# con-top-j3-0.net
KiCad netlist of a schematic drawn in Altium Designer
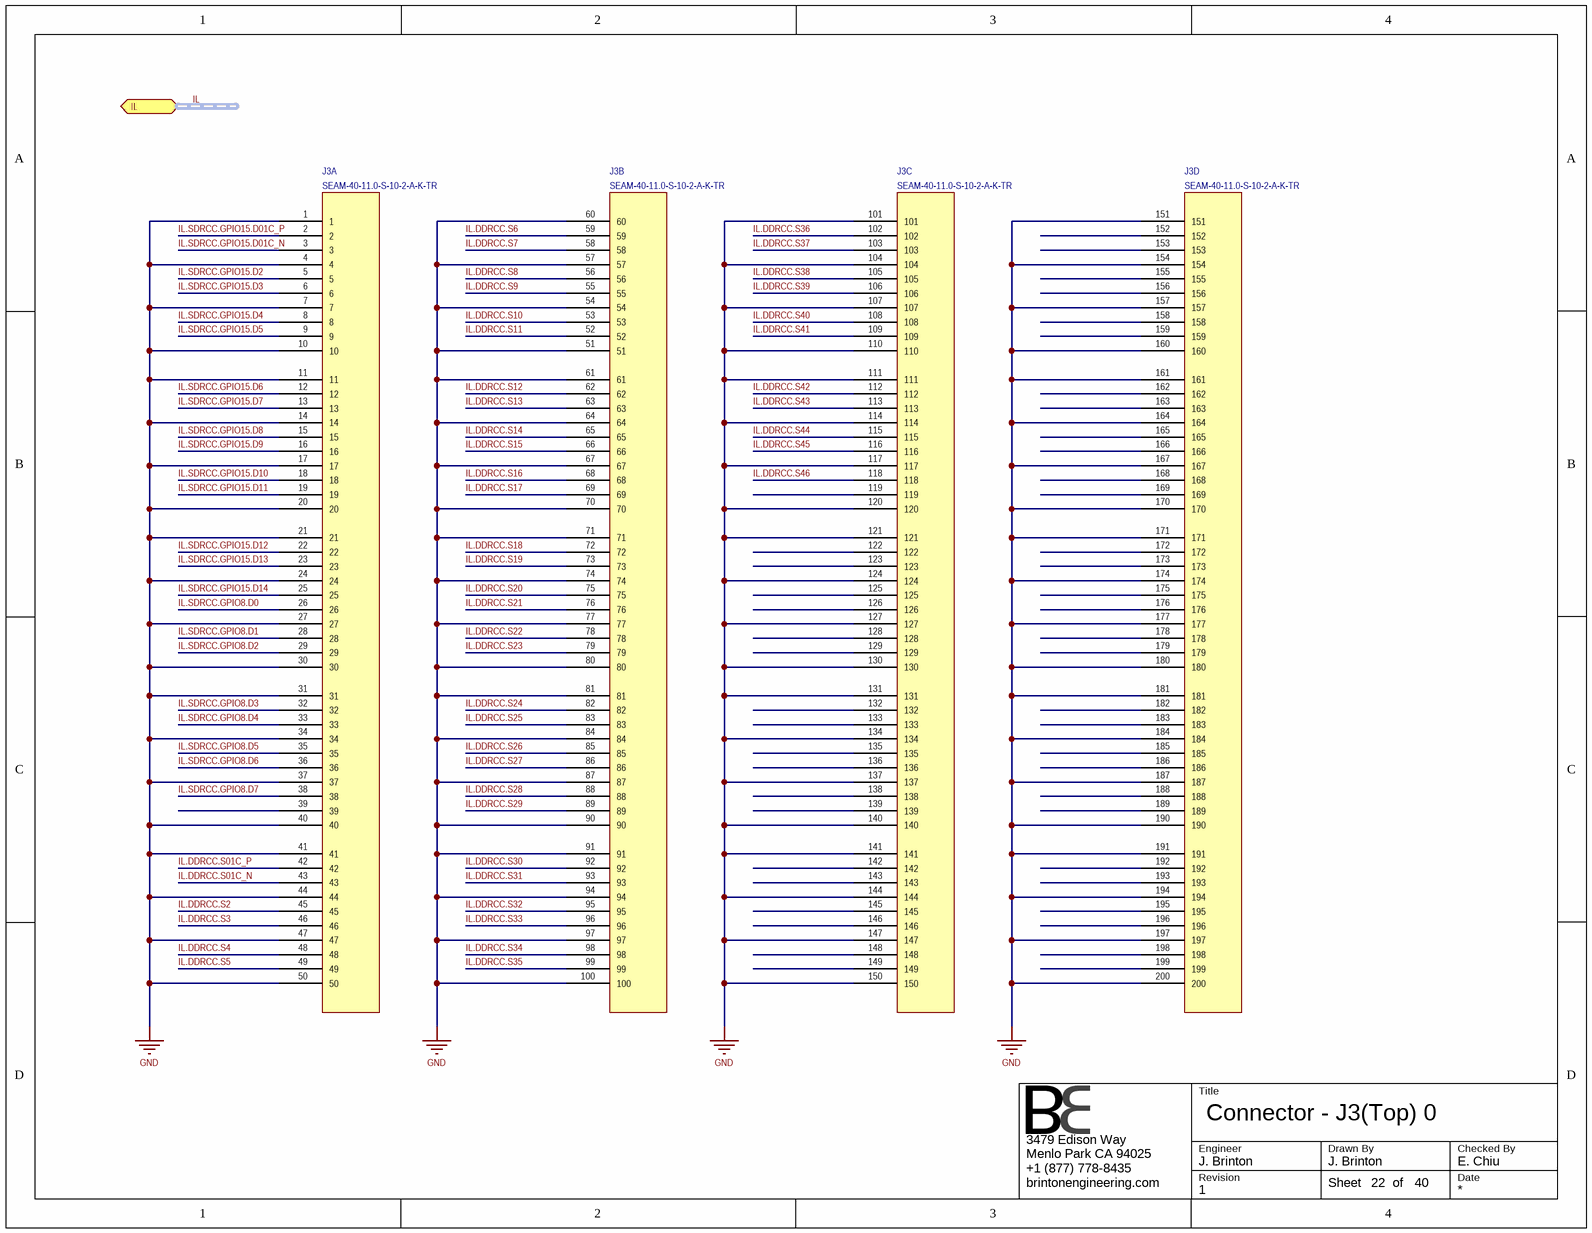
[diagram p0: con-top-j3-0.SchDoc]

(export (version "E")
  (design (tool "Eeschema 10.0.6"))
  (components
    (comp (ref "J3")
      (value "SEAM-40-11.0-S-10-2-A-K-TR")
      (footprint "samtec:SEAM-40-11.0-S-10-2-A-K-TR")
      (description "Terminal Array Assembly, Surface Mount, 0.050\" Pitch, 400 Pins")
      (fields (field (name "MANUFACTURER") "Samtec"))
      (libsource (lib "samtec") (part "SEAM-40-11.0-S-10-2-A-K-TR"))
    )
  )
  (nets
    (net (code "2") (name "/IL.DDRCC.S01C_N") (class "Default")
      (node (ref "J3") (pin "43") (pinfunction "43_43") (pintype "passive"))
    )
    (net (code "3") (name "/IL.DDRCC.S01C_P") (class "Default")
      (node (ref "J3") (pin "42") (pinfunction "42_42") (pintype "passive"))
    )
    (net (code "4") (name "/IL.DDRCC.S2") (class "Default")
      (node (ref "J3") (pin "45") (pinfunction "45_45") (pintype "passive"))
    )
    (net (code "5") (name "/IL.DDRCC.S3") (class "Default")
      (node (ref "J3") (pin "46") (pinfunction "46_46") (pintype "passive"))
    )
    (net (code "6") (name "/IL.DDRCC.S4") (class "Default")
      (node (ref "J3") (pin "48") (pinfunction "48_48") (pintype "passive"))
    )
    (net (code "7") (name "/IL.DDRCC.S5") (class "Default")
      (node (ref "J3") (pin "49") (pinfunction "49_49") (pintype "passive"))
    )
    (net (code "8") (name "/IL.DDRCC.S6") (class "Default")
      (node (ref "J3") (pin "59") (pinfunction "59_59") (pintype "passive"))
    )
    (net (code "9") (name "/IL.DDRCC.S7") (class "Default")
      (node (ref "J3") (pin "58") (pinfunction "58_58") (pintype "passive"))
    )
    (net (code "10") (name "/IL.DDRCC.S8") (class "Default")
      (node (ref "J3") (pin "56") (pinfunction "56_56") (pintype "passive"))
    )
    (net (code "11") (name "/IL.DDRCC.S9") (class "Default")
      (node (ref "J3") (pin "55") (pinfunction "55_55") (pintype "passive"))
    )
    (net (code "12") (name "/IL.DDRCC.S10") (class "Default")
      (node (ref "J3") (pin "53") (pinfunction "53_53") (pintype "passive"))
    )
    (net (code "13") (name "/IL.DDRCC.S11") (class "Default")
      (node (ref "J3") (pin "52") (pinfunction "52_52") (pintype "passive"))
    )
    (net (code "14") (name "/IL.DDRCC.S12") (class "Default")
      (node (ref "J3") (pin "62") (pinfunction "62_62") (pintype "passive"))
    )
    (net (code "15") (name "/IL.DDRCC.S13") (class "Default")
      (node (ref "J3") (pin "63") (pinfunction "63_63") (pintype "passive"))
    )
    (net (code "16") (name "/IL.DDRCC.S14") (class "Default")
      (node (ref "J3") (pin "65") (pinfunction "65_65") (pintype "passive"))
    )
    (net (code "17") (name "/IL.DDRCC.S15") (class "Default")
      (node (ref "J3") (pin "66") (pinfunction "66_66") (pintype "passive"))
    )
    (net (code "18") (name "/IL.DDRCC.S16") (class "Default")
      (node (ref "J3") (pin "68") (pinfunction "68_68") (pintype "passive"))
    )
    (net (code "19") (name "/IL.DDRCC.S17") (class "Default")
      (node (ref "J3") (pin "69") (pinfunction "69_69") (pintype "passive"))
    )
    (net (code "20") (name "/IL.DDRCC.S18") (class "Default")
      (node (ref "J3") (pin "72") (pinfunction "72_72") (pintype "passive"))
    )
    (net (code "21") (name "/IL.DDRCC.S19") (class "Default")
      (node (ref "J3") (pin "73") (pinfunction "73_73") (pintype "passive"))
    )
    (net (code "22") (name "/IL.DDRCC.S20") (class "Default")
      (node (ref "J3") (pin "75") (pinfunction "75_75") (pintype "passive"))
    )
    (net (code "23") (name "/IL.DDRCC.S21") (class "Default")
      (node (ref "J3") (pin "76") (pinfunction "76_76") (pintype "passive"))
    )
    (net (code "24") (name "/IL.DDRCC.S22") (class "Default")
      (node (ref "J3") (pin "78") (pinfunction "78_78") (pintype "passive"))
    )
    (net (code "25") (name "/IL.DDRCC.S23") (class "Default")
      (node (ref "J3") (pin "79") (pinfunction "79_79") (pintype "passive"))
    )
    (net (code "26") (name "/IL.DDRCC.S24") (class "Default")
      (node (ref "J3") (pin "82") (pinfunction "82_82") (pintype "passive"))
    )
    (net (code "27") (name "/IL.DDRCC.S25") (class "Default")
      (node (ref "J3") (pin "83") (pinfunction "83_83") (pintype "passive"))
    )
    (net (code "28") (name "/IL.DDRCC.S26") (class "Default")
      (node (ref "J3") (pin "85") (pinfunction "85_85") (pintype "passive"))
    )
    (net (code "29") (name "/IL.DDRCC.S27") (class "Default")
      (node (ref "J3") (pin "86") (pinfunction "86_86") (pintype "passive"))
    )
    (net (code "30") (name "/IL.DDRCC.S28") (class "Default")
      (node (ref "J3") (pin "88") (pinfunction "88_88") (pintype "passive"))
    )
    (net (code "31") (name "/IL.DDRCC.S29") (class "Default")
      (node (ref "J3") (pin "89") (pinfunction "89_89") (pintype "passive"))
    )
    (net (code "32") (name "/IL.DDRCC.S30") (class "Default")
      (node (ref "J3") (pin "92") (pinfunction "92_92") (pintype "passive"))
    )
    (net (code "33") (name "/IL.DDRCC.S31") (class "Default")
      (node (ref "J3") (pin "93") (pinfunction "93_93") (pintype "passive"))
    )
    (net (code "34") (name "/IL.DDRCC.S32") (class "Default")
      (node (ref "J3") (pin "95") (pinfunction "95_95") (pintype "passive"))
    )
    (net (code "35") (name "/IL.DDRCC.S33") (class "Default")
      (node (ref "J3") (pin "96") (pinfunction "96_96") (pintype "passive"))
    )
    (net (code "36") (name "/IL.DDRCC.S34") (class "Default")
      (node (ref "J3") (pin "98") (pinfunction "98_98") (pintype "passive"))
    )
    (net (code "37") (name "/IL.DDRCC.S35") (class "Default")
      (node (ref "J3") (pin "99") (pinfunction "99_99") (pintype "passive"))
    )
    (net (code "38") (name "/IL.DDRCC.S36") (class "Default")
      (node (ref "J3") (pin "102") (pinfunction "102_102") (pintype "passive"))
    )
    (net (code "39") (name "/IL.DDRCC.S37") (class "Default")
      (node (ref "J3") (pin "103") (pinfunction "103_103") (pintype "passive"))
    )
    (net (code "40") (name "/IL.DDRCC.S38") (class "Default")
      (node (ref "J3") (pin "105") (pinfunction "105_105") (pintype "passive"))
    )
    (net (code "41") (name "/IL.DDRCC.S39") (class "Default")
      (node (ref "J3") (pin "106") (pinfunction "106_106") (pintype "passive"))
    )
    (net (code "42") (name "/IL.DDRCC.S40") (class "Default")
      (node (ref "J3") (pin "108") (pinfunction "108_108") (pintype "passive"))
    )
    (net (code "43") (name "/IL.DDRCC.S41") (class "Default")
      (node (ref "J3") (pin "109") (pinfunction "109_109") (pintype "passive"))
    )
    (net (code "44") (name "/IL.DDRCC.S42") (class "Default")
      (node (ref "J3") (pin "112") (pinfunction "112_112") (pintype "passive"))
    )
    (net (code "45") (name "/IL.DDRCC.S43") (class "Default")
      (node (ref "J3") (pin "113") (pinfunction "113_113") (pintype "passive"))
    )
    (net (code "46") (name "/IL.DDRCC.S44") (class "Default")
      (node (ref "J3") (pin "115") (pinfunction "115_115") (pintype "passive"))
    )
    (net (code "47") (name "/IL.DDRCC.S45") (class "Default")
      (node (ref "J3") (pin "116") (pinfunction "116_116") (pintype "passive"))
    )
    (net (code "48") (name "/IL.DDRCC.S46") (class "Default")
      (node (ref "J3") (pin "118") (pinfunction "118_118") (pintype "passive"))
    )
    (net (code "49") (name "/IL.SDRCC.GPIO8.D0") (class "Default")
      (node (ref "J3") (pin "26") (pinfunction "26_26") (pintype "passive"))
    )
    (net (code "50") (name "/IL.SDRCC.GPIO8.D1") (class "Default")
      (node (ref "J3") (pin "28") (pinfunction "28_28") (pintype "passive"))
    )
    (net (code "51") (name "/IL.SDRCC.GPIO8.D2") (class "Default")
      (node (ref "J3") (pin "29") (pinfunction "29_29") (pintype "passive"))
    )
    (net (code "52") (name "/IL.SDRCC.GPIO8.D3") (class "Default")
      (node (ref "J3") (pin "32") (pinfunction "32_32") (pintype "passive"))
    )
    (net (code "53") (name "/IL.SDRCC.GPIO8.D4") (class "Default")
      (node (ref "J3") (pin "33") (pinfunction "33_33") (pintype "passive"))
    )
    (net (code "54") (name "/IL.SDRCC.GPIO8.D5") (class "Default")
      (node (ref "J3") (pin "35") (pinfunction "35_35") (pintype "passive"))
    )
    (net (code "55") (name "/IL.SDRCC.GPIO8.D6") (class "Default")
      (node (ref "J3") (pin "36") (pinfunction "36_36") (pintype "passive"))
    )
    (net (code "56") (name "/IL.SDRCC.GPIO8.D7") (class "Default")
      (node (ref "J3") (pin "38") (pinfunction "38_38") (pintype "passive"))
    )
    (net (code "57") (name "/IL.SDRCC.GPIO15.D01C_N") (class "Default")
      (node (ref "J3") (pin "3") (pinfunction "3_3") (pintype "passive"))
    )
    (net (code "58") (name "/IL.SDRCC.GPIO15.D01C_P") (class "Default")
      (node (ref "J3") (pin "2") (pinfunction "2_2") (pintype "passive"))
    )
    (net (code "59") (name "/IL.SDRCC.GPIO15.D2") (class "Default")
      (node (ref "J3") (pin "5") (pinfunction "5_5") (pintype "passive"))
    )
    (net (code "60") (name "/IL.SDRCC.GPIO15.D3") (class "Default")
      (node (ref "J3") (pin "6") (pinfunction "6_6") (pintype "passive"))
    )
    (net (code "61") (name "/IL.SDRCC.GPIO15.D4") (class "Default")
      (node (ref "J3") (pin "8") (pinfunction "8_8") (pintype "passive"))
    )
    (net (code "62") (name "/IL.SDRCC.GPIO15.D5") (class "Default")
      (node (ref "J3") (pin "9") (pinfunction "9_9") (pintype "passive"))
    )
    (net (code "63") (name "/IL.SDRCC.GPIO15.D6") (class "Default")
      (node (ref "J3") (pin "12") (pinfunction "12_12") (pintype "passive"))
    )
    (net (code "64") (name "/IL.SDRCC.GPIO15.D7") (class "Default")
      (node (ref "J3") (pin "13") (pinfunction "13_13") (pintype "passive"))
    )
    (net (code "65") (name "/IL.SDRCC.GPIO15.D8") (class "Default")
      (node (ref "J3") (pin "15") (pinfunction "15_15") (pintype "passive"))
    )
    (net (code "66") (name "/IL.SDRCC.GPIO15.D9") (class "Default")
      (node (ref "J3") (pin "16") (pinfunction "16_16") (pintype "passive"))
    )
    (net (code "67") (name "/IL.SDRCC.GPIO15.D10") (class "Default")
      (node (ref "J3") (pin "18") (pinfunction "18_18") (pintype "passive"))
    )
    (net (code "68") (name "/IL.SDRCC.GPIO15.D11") (class "Default")
      (node (ref "J3") (pin "19") (pinfunction "19_19") (pintype "passive"))
    )
    (net (code "69") (name "/IL.SDRCC.GPIO15.D12") (class "Default")
      (node (ref "J3") (pin "22") (pinfunction "22_22") (pintype "passive"))
    )
    (net (code "70") (name "/IL.SDRCC.GPIO15.D13") (class "Default")
      (node (ref "J3") (pin "23") (pinfunction "23_23") (pintype "passive"))
    )
    (net (code "71") (name "/IL.SDRCC.GPIO15.D14") (class "Default")
      (node (ref "J3") (pin "25") (pinfunction "25_25") (pintype "passive"))
    )
    (net (code "73") (name "GND") (class "Default")
      (node (ref "J3") (pin "1") (pinfunction "1_1") (pintype "passive"))
      (node (ref "J3") (pin "10") (pinfunction "10_10") (pintype "passive"))
      (node (ref "J3") (pin "100") (pinfunction "100_100") (pintype "passive"))
      (node (ref "J3") (pin "101") (pinfunction "101_101") (pintype "passive"))
      (node (ref "J3") (pin "104") (pinfunction "104_104") (pintype "passive"))
      (node (ref "J3") (pin "107") (pinfunction "107_107") (pintype "passive"))
      (node (ref "J3") (pin "11") (pinfunction "11_11") (pintype "passive"))
      (node (ref "J3") (pin "110") (pinfunction "110_110") (pintype "passive"))
      (node (ref "J3") (pin "111") (pinfunction "111_111") (pintype "passive"))
      (node (ref "J3") (pin "114") (pinfunction "114_114") (pintype "passive"))
      (node (ref "J3") (pin "117") (pinfunction "117_117") (pintype "passive"))
      (node (ref "J3") (pin "120") (pinfunction "120_120") (pintype "passive"))
      (node (ref "J3") (pin "121") (pinfunction "121_121") (pintype "passive"))
      (node (ref "J3") (pin "124") (pinfunction "124_124") (pintype "passive"))
      (node (ref "J3") (pin "127") (pinfunction "127_127") (pintype "passive"))
      (node (ref "J3") (pin "130") (pinfunction "130_130") (pintype "passive"))
      (node (ref "J3") (pin "131") (pinfunction "131_131") (pintype "passive"))
      (node (ref "J3") (pin "134") (pinfunction "134_134") (pintype "passive"))
      (node (ref "J3") (pin "137") (pinfunction "137_137") (pintype "passive"))
      (node (ref "J3") (pin "14") (pinfunction "14_14") (pintype "passive"))
      (node (ref "J3") (pin "140") (pinfunction "140_140") (pintype "passive"))
      (node (ref "J3") (pin "141") (pinfunction "141_141") (pintype "passive"))
      (node (ref "J3") (pin "144") (pinfunction "144_144") (pintype "passive"))
      (node (ref "J3") (pin "147") (pinfunction "147_147") (pintype "passive"))
      (node (ref "J3") (pin "150") (pinfunction "150_150") (pintype "passive"))
      (node (ref "J3") (pin "151") (pinfunction "151_151") (pintype "passive"))
      (node (ref "J3") (pin "154") (pinfunction "154_154") (pintype "passive"))
      (node (ref "J3") (pin "157") (pinfunction "157_157") (pintype "passive"))
      (node (ref "J3") (pin "160") (pinfunction "160_160") (pintype "passive"))
      (node (ref "J3") (pin "161") (pinfunction "161_161") (pintype "passive"))
      (node (ref "J3") (pin "164") (pinfunction "164_164") (pintype "passive"))
      (node (ref "J3") (pin "167") (pinfunction "167_167") (pintype "passive"))
      (node (ref "J3") (pin "17") (pinfunction "17_17") (pintype "passive"))
      (node (ref "J3") (pin "170") (pinfunction "170_170") (pintype "passive"))
      (node (ref "J3") (pin "171") (pinfunction "171_171") (pintype "passive"))
      (node (ref "J3") (pin "174") (pinfunction "174_174") (pintype "passive"))
      (node (ref "J3") (pin "177") (pinfunction "177_177") (pintype "passive"))
      (node (ref "J3") (pin "180") (pinfunction "180_180") (pintype "passive"))
      (node (ref "J3") (pin "181") (pinfunction "181_181") (pintype "passive"))
      (node (ref "J3") (pin "184") (pinfunction "184_184") (pintype "passive"))
      (node (ref "J3") (pin "187") (pinfunction "187_187") (pintype "passive"))
      (node (ref "J3") (pin "190") (pinfunction "190_190") (pintype "passive"))
      (node (ref "J3") (pin "191") (pinfunction "191_191") (pintype "passive"))
      (node (ref "J3") (pin "194") (pinfunction "194_194") (pintype "passive"))
      (node (ref "J3") (pin "197") (pinfunction "197_197") (pintype "passive"))
      (node (ref "J3") (pin "20") (pinfunction "20_20") (pintype "passive"))
      (node (ref "J3") (pin "200") (pinfunction "200_200") (pintype "passive"))
      (node (ref "J3") (pin "21") (pinfunction "21_21") (pintype "passive"))
      (node (ref "J3") (pin "24") (pinfunction "24_24") (pintype "passive"))
      (node (ref "J3") (pin "27") (pinfunction "27_27") (pintype "passive"))
      (node (ref "J3") (pin "30") (pinfunction "30_30") (pintype "passive"))
      (node (ref "J3") (pin "31") (pinfunction "31_31") (pintype "passive"))
      (node (ref "J3") (pin "34") (pinfunction "34_34") (pintype "passive"))
      (node (ref "J3") (pin "37") (pinfunction "37_37") (pintype "passive"))
      (node (ref "J3") (pin "4") (pinfunction "4_4") (pintype "passive"))
      (node (ref "J3") (pin "40") (pinfunction "40_40") (pintype "passive"))
      (node (ref "J3") (pin "41") (pinfunction "41_41") (pintype "passive"))
      (node (ref "J3") (pin "44") (pinfunction "44_44") (pintype "passive"))
      (node (ref "J3") (pin "47") (pinfunction "47_47") (pintype "passive"))
      (node (ref "J3") (pin "50") (pinfunction "50_50") (pintype "passive"))
      (node (ref "J3") (pin "51") (pinfunction "51_51") (pintype "passive"))
      (node (ref "J3") (pin "54") (pinfunction "54_54") (pintype "passive"))
      (node (ref "J3") (pin "57") (pinfunction "57_57") (pintype "passive"))
      (node (ref "J3") (pin "60") (pinfunction "60_60") (pintype "passive"))
      (node (ref "J3") (pin "61") (pinfunction "61_61") (pintype "passive"))
      (node (ref "J3") (pin "64") (pinfunction "64_64") (pintype "passive"))
      (node (ref "J3") (pin "67") (pinfunction "67_67") (pintype "passive"))
      (node (ref "J3") (pin "7") (pinfunction "7_7") (pintype "passive"))
      (node (ref "J3") (pin "70") (pinfunction "70_70") (pintype "passive"))
      (node (ref "J3") (pin "71") (pinfunction "71_71") (pintype "passive"))
      (node (ref "J3") (pin "74") (pinfunction "74_74") (pintype "passive"))
      (node (ref "J3") (pin "77") (pinfunction "77_77") (pintype "passive"))
      (node (ref "J3") (pin "80") (pinfunction "80_80") (pintype "passive"))
      (node (ref "J3") (pin "81") (pinfunction "81_81") (pintype "passive"))
      (node (ref "J3") (pin "84") (pinfunction "84_84") (pintype "passive"))
      (node (ref "J3") (pin "87") (pinfunction "87_87") (pintype "passive"))
      (node (ref "J3") (pin "90") (pinfunction "90_90") (pintype "passive"))
      (node (ref "J3") (pin "91") (pinfunction "91_91") (pintype "passive"))
      (node (ref "J3") (pin "94") (pinfunction "94_94") (pintype "passive"))
      (node (ref "J3") (pin "97") (pinfunction "97_97") (pintype "passive"))
    )
    (net (code "74") (name "unconnected-(J3-Pad39)") (class "Default")
      (node (ref "J3") (pin "39") (pinfunction "39_39") (pintype "passive"))
    )
    (net (code "75") (name "unconnected-(J3-Pad119)") (class "Default")
      (node (ref "J3") (pin "119") (pinfunction "119_119") (pintype "passive"))
    )
    (net (code "76") (name "unconnected-(J3-Pad122)") (class "Default")
      (node (ref "J3") (pin "122") (pinfunction "122_122") (pintype "passive"))
    )
    (net (code "77") (name "unconnected-(J3-Pad123)") (class "Default")
      (node (ref "J3") (pin "123") (pinfunction "123_123") (pintype "passive"))
    )
    (net (code "78") (name "unconnected-(J3-Pad125)") (class "Default")
      (node (ref "J3") (pin "125") (pinfunction "125_125") (pintype "passive"))
    )
    (net (code "79") (name "unconnected-(J3-Pad126)") (class "Default")
      (node (ref "J3") (pin "126") (pinfunction "126_126") (pintype "passive"))
    )
    (net (code "80") (name "unconnected-(J3-Pad128)") (class "Default")
      (node (ref "J3") (pin "128") (pinfunction "128_128") (pintype "passive"))
    )
    (net (code "81") (name "unconnected-(J3-Pad129)") (class "Default")
      (node (ref "J3") (pin "129") (pinfunction "129_129") (pintype "passive"))
    )
    (net (code "82") (name "unconnected-(J3-Pad132)") (class "Default")
      (node (ref "J3") (pin "132") (pinfunction "132_132") (pintype "passive"))
    )
    (net (code "83") (name "unconnected-(J3-Pad133)") (class "Default")
      (node (ref "J3") (pin "133") (pinfunction "133_133") (pintype "passive"))
    )
    (net (code "84") (name "unconnected-(J3-Pad135)") (class "Default")
      (node (ref "J3") (pin "135") (pinfunction "135_135") (pintype "passive"))
    )
    (net (code "85") (name "unconnected-(J3-Pad136)") (class "Default")
      (node (ref "J3") (pin "136") (pinfunction "136_136") (pintype "passive"))
    )
    (net (code "86") (name "unconnected-(J3-Pad138)") (class "Default")
      (node (ref "J3") (pin "138") (pinfunction "138_138") (pintype "passive"))
    )
    (net (code "87") (name "unconnected-(J3-Pad139)") (class "Default")
      (node (ref "J3") (pin "139") (pinfunction "139_139") (pintype "passive"))
    )
    (net (code "88") (name "unconnected-(J3-Pad142)") (class "Default")
      (node (ref "J3") (pin "142") (pinfunction "142_142") (pintype "passive"))
    )
    (net (code "89") (name "unconnected-(J3-Pad143)") (class "Default")
      (node (ref "J3") (pin "143") (pinfunction "143_143") (pintype "passive"))
    )
    (net (code "90") (name "unconnected-(J3-Pad145)") (class "Default")
      (node (ref "J3") (pin "145") (pinfunction "145_145") (pintype "passive"))
    )
    (net (code "91") (name "unconnected-(J3-Pad146)") (class "Default")
      (node (ref "J3") (pin "146") (pinfunction "146_146") (pintype "passive"))
    )
    (net (code "92") (name "unconnected-(J3-Pad148)") (class "Default")
      (node (ref "J3") (pin "148") (pinfunction "148_148") (pintype "passive"))
    )
    (net (code "93") (name "unconnected-(J3-Pad149)") (class "Default")
      (node (ref "J3") (pin "149") (pinfunction "149_149") (pintype "passive"))
    )
    (net (code "94") (name "unconnected-(J3-Pad152)") (class "Default")
      (node (ref "J3") (pin "152") (pinfunction "152_152") (pintype "passive"))
    )
    (net (code "95") (name "unconnected-(J3-Pad153)") (class "Default")
      (node (ref "J3") (pin "153") (pinfunction "153_153") (pintype "passive"))
    )
    (net (code "96") (name "unconnected-(J3-Pad155)") (class "Default")
      (node (ref "J3") (pin "155") (pinfunction "155_155") (pintype "passive"))
    )
    (net (code "97") (name "unconnected-(J3-Pad156)") (class "Default")
      (node (ref "J3") (pin "156") (pinfunction "156_156") (pintype "passive"))
    )
    (net (code "98") (name "unconnected-(J3-Pad158)") (class "Default")
      (node (ref "J3") (pin "158") (pinfunction "158_158") (pintype "passive"))
    )
    (net (code "99") (name "unconnected-(J3-Pad159)") (class "Default")
      (node (ref "J3") (pin "159") (pinfunction "159_159") (pintype "passive"))
    )
    (net (code "100") (name "unconnected-(J3-Pad162)") (class "Default")
      (node (ref "J3") (pin "162") (pinfunction "162_162") (pintype "passive"))
    )
    (net (code "101") (name "unconnected-(J3-Pad163)") (class "Default")
      (node (ref "J3") (pin "163") (pinfunction "163_163") (pintype "passive"))
    )
    (net (code "102") (name "unconnected-(J3-Pad165)") (class "Default")
      (node (ref "J3") (pin "165") (pinfunction "165_165") (pintype "passive"))
    )
    (net (code "103") (name "unconnected-(J3-Pad166)") (class "Default")
      (node (ref "J3") (pin "166") (pinfunction "166_166") (pintype "passive"))
    )
    (net (code "104") (name "unconnected-(J3-Pad168)") (class "Default")
      (node (ref "J3") (pin "168") (pinfunction "168_168") (pintype "passive"))
    )
    (net (code "105") (name "unconnected-(J3-Pad169)") (class "Default")
      (node (ref "J3") (pin "169") (pinfunction "169_169") (pintype "passive"))
    )
    (net (code "106") (name "unconnected-(J3-Pad172)") (class "Default")
      (node (ref "J3") (pin "172") (pinfunction "172_172") (pintype "passive"))
    )
    (net (code "107") (name "unconnected-(J3-Pad173)") (class "Default")
      (node (ref "J3") (pin "173") (pinfunction "173_173") (pintype "passive"))
    )
    (net (code "108") (name "unconnected-(J3-Pad175)") (class "Default")
      (node (ref "J3") (pin "175") (pinfunction "175_175") (pintype "passive"))
    )
    (net (code "109") (name "unconnected-(J3-Pad176)") (class "Default")
      (node (ref "J3") (pin "176") (pinfunction "176_176") (pintype "passive"))
    )
    (net (code "110") (name "unconnected-(J3-Pad178)") (class "Default")
      (node (ref "J3") (pin "178") (pinfunction "178_178") (pintype "passive"))
    )
    (net (code "111") (name "unconnected-(J3-Pad179)") (class "Default")
      (node (ref "J3") (pin "179") (pinfunction "179_179") (pintype "passive"))
    )
    (net (code "112") (name "unconnected-(J3-Pad182)") (class "Default")
      (node (ref "J3") (pin "182") (pinfunction "182_182") (pintype "passive"))
    )
    (net (code "113") (name "unconnected-(J3-Pad183)") (class "Default")
      (node (ref "J3") (pin "183") (pinfunction "183_183") (pintype "passive"))
    )
    (net (code "114") (name "unconnected-(J3-Pad185)") (class "Default")
      (node (ref "J3") (pin "185") (pinfunction "185_185") (pintype "passive"))
    )
    (net (code "115") (name "unconnected-(J3-Pad186)") (class "Default")
      (node (ref "J3") (pin "186") (pinfunction "186_186") (pintype "passive"))
    )
    (net (code "116") (name "unconnected-(J3-Pad188)") (class "Default")
      (node (ref "J3") (pin "188") (pinfunction "188_188") (pintype "passive"))
    )
    (net (code "117") (name "unconnected-(J3-Pad189)") (class "Default")
      (node (ref "J3") (pin "189") (pinfunction "189_189") (pintype "passive"))
    )
    (net (code "118") (name "unconnected-(J3-Pad192)") (class "Default")
      (node (ref "J3") (pin "192") (pinfunction "192_192") (pintype "passive"))
    )
    (net (code "119") (name "unconnected-(J3-Pad193)") (class "Default")
      (node (ref "J3") (pin "193") (pinfunction "193_193") (pintype "passive"))
    )
    (net (code "120") (name "unconnected-(J3-Pad195)") (class "Default")
      (node (ref "J3") (pin "195") (pinfunction "195_195") (pintype "passive"))
    )
    (net (code "121") (name "unconnected-(J3-Pad196)") (class "Default")
      (node (ref "J3") (pin "196") (pinfunction "196_196") (pintype "passive"))
    )
    (net (code "122") (name "unconnected-(J3-Pad198)") (class "Default")
      (node (ref "J3") (pin "198") (pinfunction "198_198") (pintype "passive"))
    )
    (net (code "123") (name "unconnected-(J3-Pad199)") (class "Default")
      (node (ref "J3") (pin "199") (pinfunction "199_199") (pintype "passive"))
    )
  )
)
